# clock.net
KiCad netlist of a schematic drawn in Altium Designer
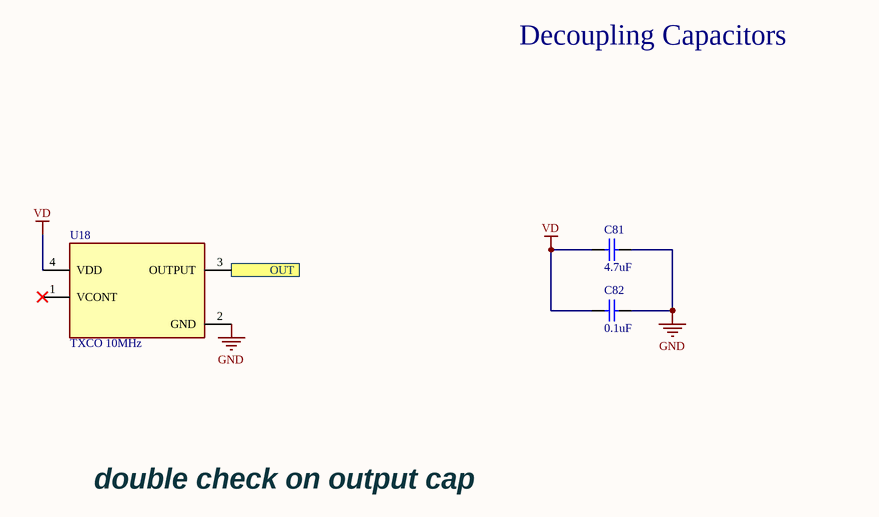
[diagram p0: clock.SchDoc]

(export (version "E")
  (design (tool "Eeschema 10.0.6"))
  (components
    (comp (ref "C81")
      (value "4.7uF")
      (footprint "STD_0805_C")
      (description "Capacitor, 4.7uF, 0805")
      (libsource (lib "Arturo_Approved") (part "CL21A475KAQNNNE"))
    )
    (comp (ref "C82")
      (value "0.1uF")
      (footprint "STD_0805_C")
      (description "Capacitor, 0.1uF, 0805")
      (libsource (lib "Arturo_Approved") (part "CL21B104KACNNNC"))
    )
    (comp (ref "U18")
      (value "TXCO 10MHz")
      (footprint "OSC_ECS-TXO-3225-100-TR")
      (description "10 Mhz osc")
      (libsource (lib "Arturo_Approved") (part "ECS-TXO-3225-100-TR"))
    )
  )
  (nets
    (net (code "1") (name "/OUT") (class "Default")
      (node (ref "U18") (pin "3") (pinfunction "OUTPUT_3") (pintype "passive"))
    )
    (net (code "2") (name "GND") (class "Default")
      (node (ref "C81") (pin "2") (pinfunction "2_2") (pintype "passive"))
      (node (ref "C82") (pin "2") (pinfunction "2_2") (pintype "passive"))
      (node (ref "U18") (pin "2") (pinfunction "GND_2") (pintype "power_in"))
    )
    (net (code "3") (name "VD") (class "Default")
      (node (ref "C81") (pin "1") (pinfunction "1_1") (pintype "passive"))
      (node (ref "C82") (pin "1") (pinfunction "1_1") (pintype "passive"))
      (node (ref "U18") (pin "4") (pinfunction "VDD_4") (pintype "passive"))
    )
    (net (code "4") (name "unconnected-(U18-VCONT-Pad1)") (class "Default")
      (node (ref "U18") (pin "1") (pinfunction "VCONT_1") (pintype "passive+no_connect"))
    )
  )
)
